# USART_IrDA.net
KiCad netlist of a schematic drawn in Altium Designer
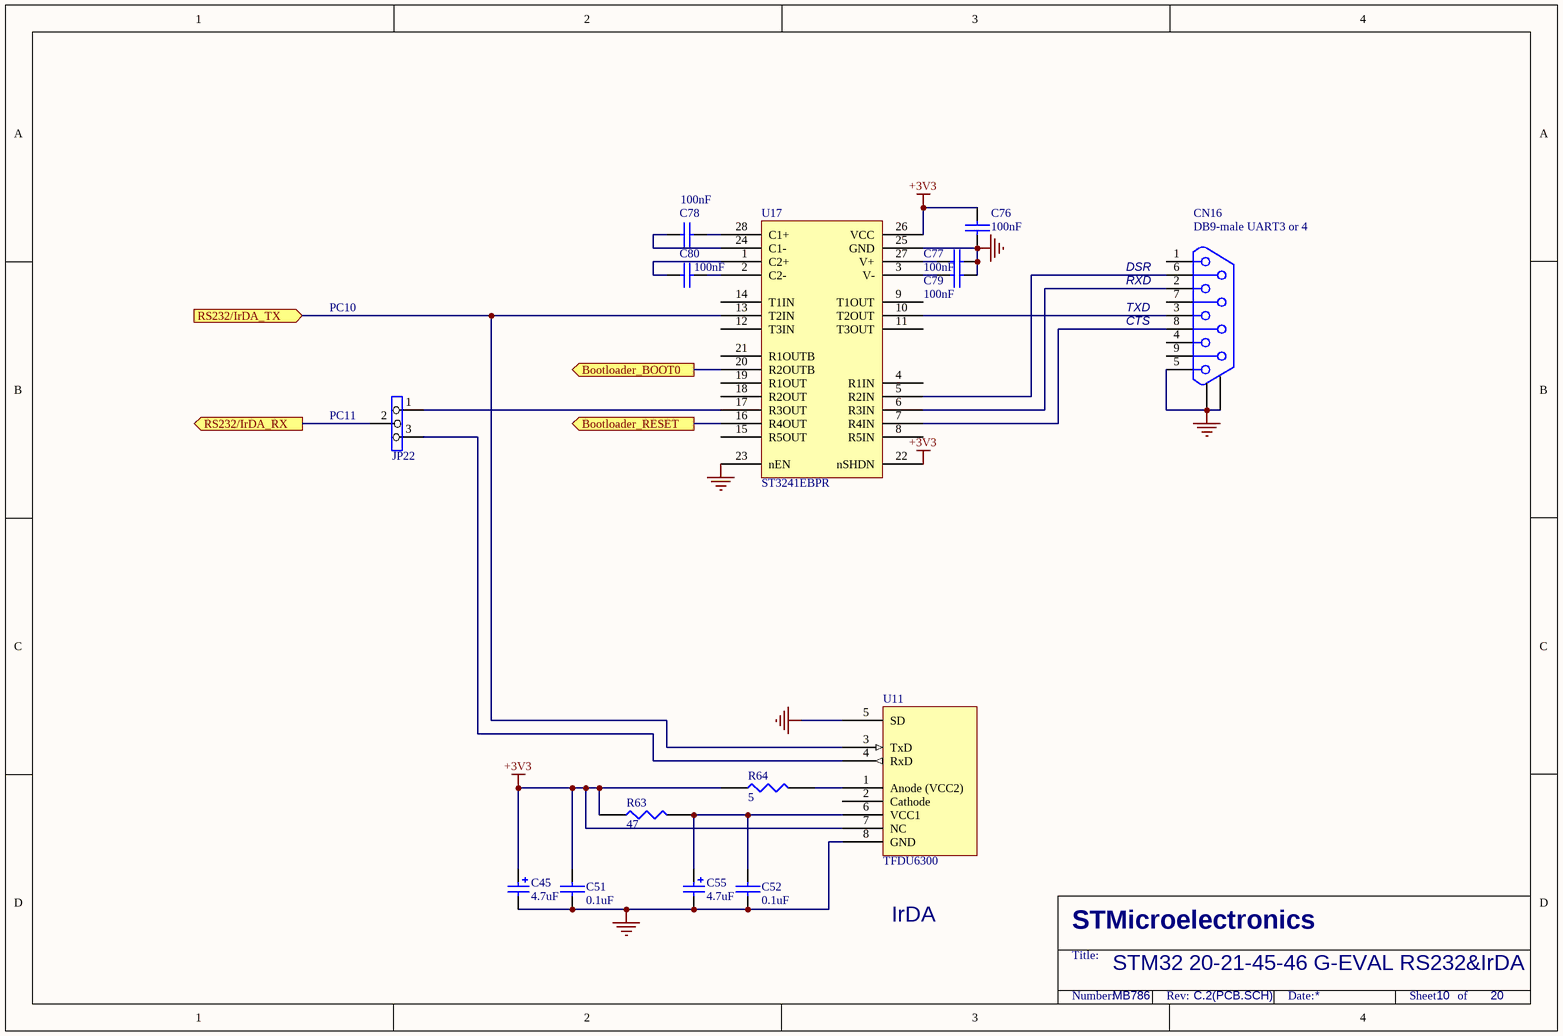
[diagram p0: USART&IrDA.SchDoc]

(export (version "E")
  (design (tool "Eeschema 10.0.6"))
  (components
    (comp (ref "C45")
      (value "4.7uF")
      (footprint "TAN-A")
      (description "Polarized Capacitor (Radial)")
      (fields (field (name "PUBLISHER") "Altium Limited"))
      (libsource (lib "Miscellaneous Devices") (part "Cap Pol1"))
    )
    (comp (ref "C51")
      (value "0.1uF")
      (footprint "0402C")
      (description "Capacitor")
      (libsource (lib "*") (part "CAP"))
    )
    (comp (ref "C52")
      (value "0.1uF")
      (footprint "0402C")
      (description "Capacitor")
      (libsource (lib "*") (part "CAP"))
    )
    (comp (ref "C55")
      (value "4.7uF")
      (footprint "TAN-A")
      (description "Polarized Capacitor (Radial)")
      (fields (field (name "PUBLISHER") "Altium Limited"))
      (libsource (lib "Miscellaneous Devices") (part "Cap Pol1"))
    )
    (comp (ref "C76")
      (value "100nF")
      (footprint "0402C")
      (description "Capacitor")
      (libsource (lib "*") (part "CAP"))
    )
    (comp (ref "C77")
      (value "100nF")
      (footprint "0402C")
      (description "Capacitor")
      (libsource (lib "*") (part "CAP"))
    )
    (comp (ref "C78")
      (value "100nF")
      (footprint "0402C")
      (description "Capacitor")
      (libsource (lib "*") (part "CAP"))
    )
    (comp (ref "C79")
      (value "100nF")
      (footprint "0402C")
      (description "Capacitor")
      (libsource (lib "*") (part "CAP"))
    )
    (comp (ref "C80")
      (value "100nF")
      (footprint "0402C")
      (description "Capacitor")
      (libsource (lib "*") (part "CAP"))
    )
    (comp (ref "CN16") (value "DB9-male UART3 or 4") (footprint "DB9/M") (libsource (lib "*") (part "DB9")))
    (comp (ref "JP22") (value "~") (footprint "SIP3") (libsource (lib "STR910_SCHLIB") (part "Jumper3")))
    (comp (ref "R63") (value "47") (footprint "0603R") (libsource (lib "*") (part "RES1")))
    (comp (ref "R64") (value "5") (footprint "0603R") (libsource (lib "*") (part "RES1")))
    (comp (ref "U11")
      (value "TFDU6300")
      (footprint "IR_VISHAY3")
      (description "TFDU4300")
      (libsource (lib "*") (part "TFDU4300"))
    )
    (comp (ref "U17") (value "ST3241EBPR") (footprint "SSOP28") (libsource (lib "*") (part "ST3241")))
  )
  (nets
    (net (code "1") (name "+3V3") (class "Default")
      (node (ref "C45") (pin "1") (pinfunction "1_1") (pintype "passive"))
      (node (ref "C51") (pin "1") (pinfunction "1_1") (pintype "passive"))
      (node (ref "C76") (pin "2") (pinfunction "2_2") (pintype "passive"))
      (node (ref "R63") (pin "1") (pinfunction "1_1") (pintype "passive"))
      (node (ref "R64") (pin "1") (pinfunction "1_1") (pintype "passive"))
      (node (ref "U11") (pin "7") (pinfunction "NC_7") (pintype "passive"))
      (node (ref "U17") (pin "22") (pinfunction "nSHDN_22") (pintype "passive"))
      (node (ref "U17") (pin "26") (pinfunction "VCC_26") (pintype "passive"))
    )
    (net (code "2") (name "/Bootloader_BOOT0") (class "Default")
      (node (ref "U17") (pin "20") (pinfunction "R2OUTB_20") (pintype "passive"))
    )
    (net (code "3") (name "/Bootloader_RESET") (class "Default")
      (node (ref "U17") (pin "16") (pinfunction "R4OUT_16") (pintype "passive"))
    )
    (net (code "4") (name "/RS232{slash}IrDA_RX") (class "Default")
      (node (ref "JP22") (pin "2") (pintype "passive"))
    )
    (net (code "5") (name "/RS232{slash}IrDA_TX") (class "Default")
      (node (ref "U11") (pin "3") (pinfunction "TxD_3") (pintype "input"))
      (node (ref "U17") (pin "13") (pinfunction "T2IN_13") (pintype "passive"))
    )
    (net (code "6") (name "GND") (class "Default")
      (node (ref "C45") (pin "2") (pinfunction "2_2") (pintype "passive"))
      (node (ref "C51") (pin "2") (pinfunction "2_2") (pintype "passive"))
      (node (ref "C52") (pin "2") (pinfunction "2_2") (pintype "passive"))
      (node (ref "C55") (pin "2") (pinfunction "2_2") (pintype "passive"))
      (node (ref "C76") (pin "1") (pinfunction "1_1") (pintype "passive"))
      (node (ref "C77") (pin "2") (pinfunction "2_2") (pintype "passive"))
      (node (ref "C79") (pin "2") (pinfunction "2_2") (pintype "passive"))
      (node (ref "CN16") (pin "0") (pinfunction "10_0") (pintype "passive"))
      (node (ref "CN16") (pin "5") (pinfunction "5_5") (pintype "passive"))
      (node (ref "U11") (pin "5") (pinfunction "SD_5") (pintype "passive"))
      (node (ref "U11") (pin "8") (pinfunction "GND_8") (pintype "passive"))
      (node (ref "U17") (pin "23") (pinfunction "nEN_23") (pintype "passive"))
      (node (ref "U17") (pin "25") (pinfunction "GND_25") (pintype "passive"))
    )
    (net (code "7") (name "Net-(U11-Anode_(VCC2))") (class "Default")
      (node (ref "R64") (pin "2") (pinfunction "2_2") (pintype "passive"))
      (node (ref "U11") (pin "1") (pinfunction "Anode_(VCC2)_1") (pintype "passive"))
    )
    (net (code "8") (name "Net-(U11-RxD)") (class "Default")
      (node (ref "JP22") (pin "3") (pintype "passive"))
      (node (ref "U11") (pin "4") (pinfunction "RxD_4") (pintype "output"))
    )
    (net (code "9") (name "Net-(U11-VCC1)") (class "Default")
      (node (ref "C52") (pin "1") (pinfunction "1_1") (pintype "passive"))
      (node (ref "C55") (pin "1") (pinfunction "1_1") (pintype "passive"))
      (node (ref "R63") (pin "2") (pinfunction "2_2") (pintype "passive"))
      (node (ref "U11") (pin "6") (pinfunction "VCC1_6") (pintype "passive"))
    )
    (net (code "10") (name "Net-(U17-C1+)") (class "Default")
      (node (ref "C78") (pin "2") (pinfunction "2_2") (pintype "passive"))
      (node (ref "U17") (pin "28") (pinfunction "C1+_28") (pintype "passive"))
    )
    (net (code "11") (name "Net-(U17-C1-)") (class "Default")
      (node (ref "C78") (pin "1") (pinfunction "1_1") (pintype "passive"))
      (node (ref "U17") (pin "24") (pinfunction "C1-_24") (pintype "passive"))
    )
    (net (code "12") (name "Net-(U17-C2+)") (class "Default")
      (node (ref "C80") (pin "1") (pinfunction "1_1") (pintype "passive"))
      (node (ref "U17") (pin "1") (pinfunction "C2+_1") (pintype "passive"))
    )
    (net (code "13") (name "Net-(U17-C2-)") (class "Default")
      (node (ref "C80") (pin "2") (pinfunction "2_2") (pintype "passive"))
      (node (ref "U17") (pin "2") (pinfunction "C2-_2") (pintype "passive"))
    )
    (net (code "14") (name "Net-(U17-R2IN)") (class "Default")
      (node (ref "CN16") (pin "6") (pinfunction "6_6") (pintype "passive"))
      (node (ref "U17") (pin "5") (pinfunction "R2IN_5") (pintype "passive"))
    )
    (net (code "15") (name "Net-(U17-R3IN)") (class "Default")
      (node (ref "CN16") (pin "2") (pinfunction "2_2") (pintype "passive"))
      (node (ref "U17") (pin "6") (pinfunction "R3IN_6") (pintype "passive"))
    )
    (net (code "16") (name "Net-(U17-R3OUT)") (class "Default")
      (node (ref "JP22") (pin "1") (pintype "passive"))
      (node (ref "U17") (pin "17") (pinfunction "R3OUT_17") (pintype "passive"))
    )
    (net (code "17") (name "Net-(U17-R4IN)") (class "Default")
      (node (ref "CN16") (pin "8") (pinfunction "8_8") (pintype "passive"))
      (node (ref "U17") (pin "7") (pinfunction "R4IN_7") (pintype "passive"))
    )
    (net (code "18") (name "Net-(U17-T2OUT)") (class "Default")
      (node (ref "CN16") (pin "3") (pinfunction "3_3") (pintype "passive"))
      (node (ref "U17") (pin "10") (pinfunction "T2OUT_10") (pintype "passive"))
    )
    (net (code "19") (name "Net-(U17-V+)") (class "Default")
      (node (ref "C77") (pin "1") (pinfunction "1_1") (pintype "passive"))
      (node (ref "U17") (pin "27") (pinfunction "V+_27") (pintype "passive"))
    )
    (net (code "20") (name "Net-(U17-V-)") (class "Default")
      (node (ref "C79") (pin "1") (pinfunction "1_1") (pintype "passive"))
      (node (ref "U17") (pin "3") (pinfunction "V-_3") (pintype "passive"))
    )
    (net (code "21") (name "unconnected-(CN16-Pad1)") (class "Default")
      (node (ref "CN16") (pin "1") (pinfunction "1_1") (pintype "passive"))
    )
    (net (code "22") (name "unconnected-(CN16-Pad4)") (class "Default")
      (node (ref "CN16") (pin "4") (pinfunction "4_4") (pintype "passive"))
    )
    (net (code "23") (name "unconnected-(CN16-Pad7)") (class "Default")
      (node (ref "CN16") (pin "7") (pinfunction "7_7") (pintype "passive"))
    )
    (net (code "24") (name "unconnected-(CN16-Pad9)") (class "Default")
      (node (ref "CN16") (pin "9") (pinfunction "9_9") (pintype "passive"))
    )
    (net (code "25") (name "unconnected-(U11-Cathode-Pad2)") (class "Default")
      (node (ref "U11") (pin "2") (pinfunction "Cathode_2") (pintype "passive"))
    )
    (net (code "26") (name "unconnected-(U17-R1IN-Pad4)") (class "Default")
      (node (ref "U17") (pin "4") (pinfunction "R1IN_4") (pintype "passive"))
    )
    (net (code "27") (name "unconnected-(U17-R1OUT-Pad19)") (class "Default")
      (node (ref "U17") (pin "19") (pinfunction "R1OUT_19") (pintype "passive"))
    )
    (net (code "28") (name "unconnected-(U17-R1OUTB-Pad21)") (class "Default")
      (node (ref "U17") (pin "21") (pinfunction "R1OUTB_21") (pintype "passive"))
    )
    (net (code "29") (name "unconnected-(U17-R2OUT-Pad18)") (class "Default")
      (node (ref "U17") (pin "18") (pinfunction "R2OUT_18") (pintype "passive"))
    )
    (net (code "30") (name "unconnected-(U17-R5IN-Pad8)") (class "Default")
      (node (ref "U17") (pin "8") (pinfunction "R5IN_8") (pintype "passive"))
    )
    (net (code "31") (name "unconnected-(U17-R5OUT-Pad15)") (class "Default")
      (node (ref "U17") (pin "15") (pinfunction "R5OUT_15") (pintype "passive"))
    )
    (net (code "32") (name "unconnected-(U17-T1IN-Pad14)") (class "Default")
      (node (ref "U17") (pin "14") (pinfunction "T1IN_14") (pintype "passive"))
    )
    (net (code "33") (name "unconnected-(U17-T1OUT-Pad9)") (class "Default")
      (node (ref "U17") (pin "9") (pinfunction "T1OUT_9") (pintype "passive"))
    )
    (net (code "34") (name "unconnected-(U17-T3IN-Pad12)") (class "Default")
      (node (ref "U17") (pin "12") (pinfunction "T3IN_12") (pintype "passive"))
    )
    (net (code "35") (name "unconnected-(U17-T3OUT-Pad11)") (class "Default")
      (node (ref "U17") (pin "11") (pinfunction "T3OUT_11") (pintype "passive"))
    )
  )
)
